# Display.net
KiCad netlist of a schematic drawn in Altium Designer
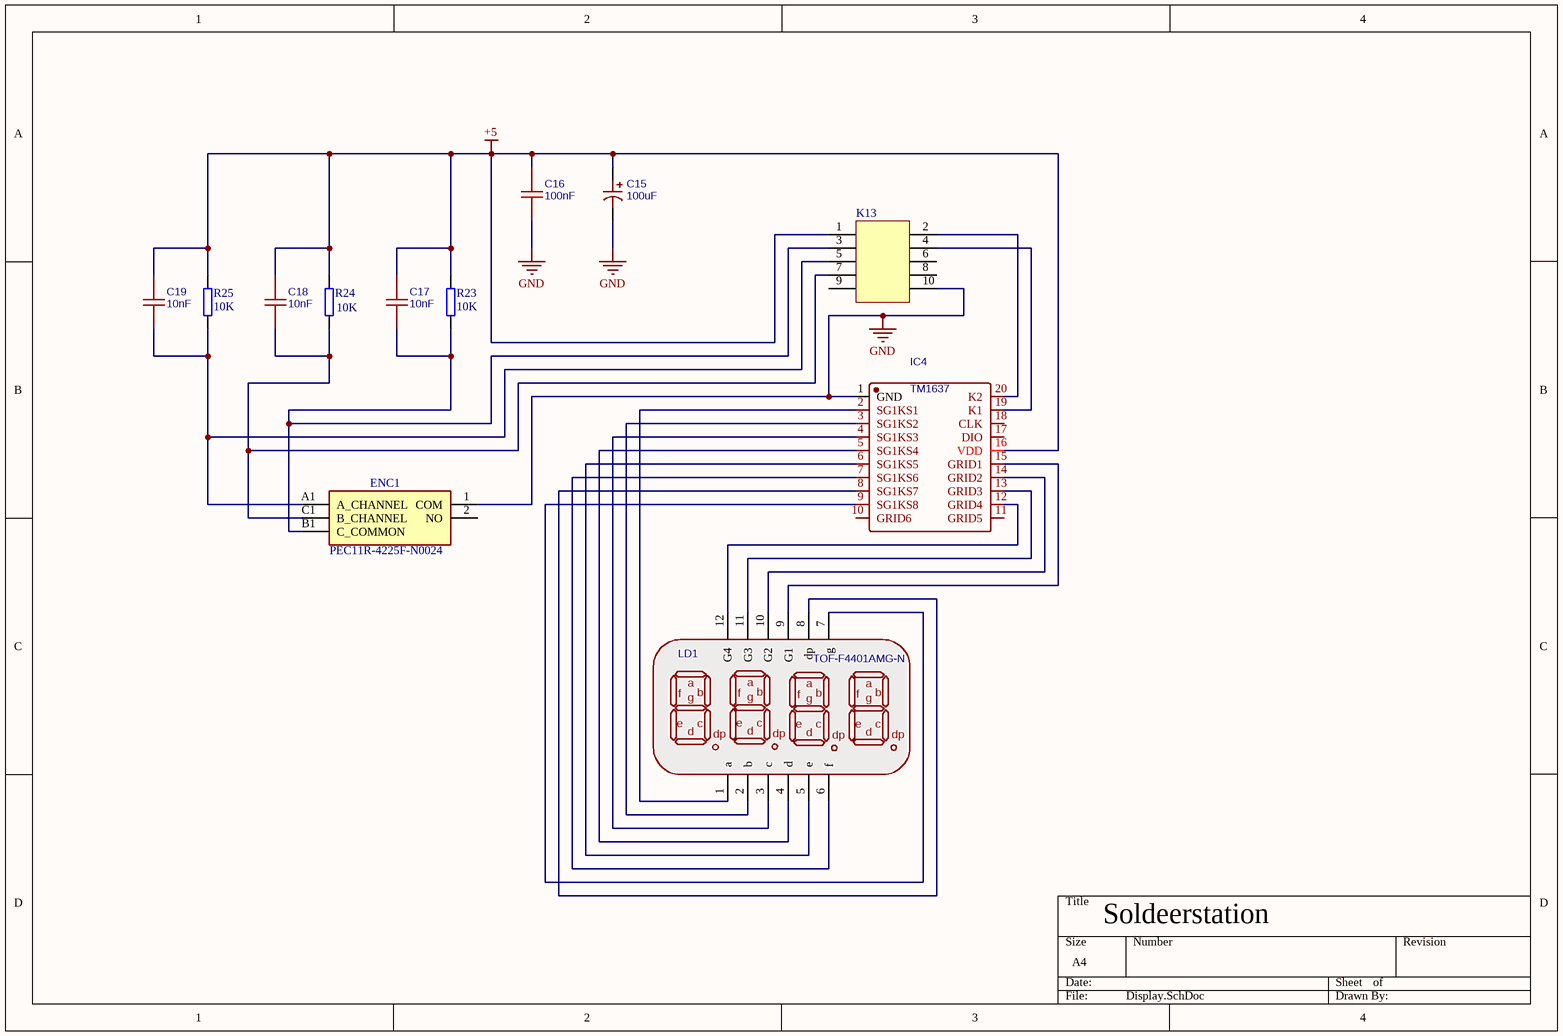
[diagram p0: Display.SchDoc]

(export (version "E")
  (design (tool "Eeschema 10.0.6"))
  (components
    (comp (ref "C15")
      (value "100uF")
      (footprint "C4 100uF")
      (fields
        (field (name "BOM_SUPPLIER PART") "C445063")
        (field (name "BOM_MANUFACTURER PART") "UWT1H101MNL1GS")
        (field (name "CONTRIBUTOR") "LCSC")
      )
      (libsource (lib "SoldeerStation") (part "C4 100uF"))
    )
    (comp (ref "C16")
      (value "100nF")
      (footprint "C6,7,12,13 10nF")
      (fields
        (field (name "BOM_SUPPLIER PART") "C376921")
        (field (name "BOM_MANUFACTURER PART") "TCC0805X7R103M500DT")
        (field (name "CONTRIBUTOR") "LCSC")
      )
      (libsource (lib "SoldeerStation") (part "C6,7,12,13 10nF"))
    )
    (comp (ref "C17")
      (value "10nF")
      (footprint "C6,7,12,13 10nF")
      (fields
        (field (name "BOM_SUPPLIER PART") "C376921")
        (field (name "BOM_MANUFACTURER PART") "TCC0805X7R103M500DT")
        (field (name "CONTRIBUTOR") "LCSC")
      )
      (libsource (lib "SoldeerStation") (part "C6,7,12,13 10nF"))
    )
    (comp (ref "C18")
      (value "10nF")
      (footprint "C6,7,12,13 10nF")
      (fields
        (field (name "BOM_SUPPLIER PART") "C376921")
        (field (name "BOM_MANUFACTURER PART") "TCC0805X7R103M500DT")
        (field (name "CONTRIBUTOR") "LCSC")
      )
      (libsource (lib "SoldeerStation") (part "C6,7,12,13 10nF"))
    )
    (comp (ref "C19")
      (value "10nF")
      (footprint "C6,7,12,13 10nF")
      (fields
        (field (name "BOM_SUPPLIER PART") "C376921")
        (field (name "BOM_MANUFACTURER PART") "TCC0805X7R103M500DT")
        (field (name "CONTRIBUTOR") "LCSC")
      )
      (libsource (lib "SoldeerStation") (part "C6,7,12,13 10nF"))
    )
    (comp (ref "ENC1")
      (value "PEC11R-4225F-N0024")
      (footprint "ENC1 draai encoder")
      (fields (field (name "MOUSER PART NUMBER") "652-PEC11R-4225F-N24"))
      (libsource (lib "SoldeerStation") (part "ENC1 Draai encoder"))
    )
    (comp (ref "IC4")
      (value "TM1637")
      (footprint "IC4 Led driver")
      (description "TM1637(TA2007)")
      (fields (field (name "BOM_SUPPLIER PART") "C5337160") (field (name "CONTRIBUTOR") "lcsc"))
      (libsource (lib "SoldeerStation") (part "IC4 Led driver"))
    )
    (comp (ref "K13")
      (value "~")
      (footprint "BOxHeader_10")
      (libsource (lib "SoldeerStation") (part "K Boxheader_10"))
    )
    (comp (ref "LD1")
      (value "TOF-F4401AMG-N")
      (footprint "LED1")
      (fields (field (name "BOM_SUPPLIER PART") "C325426") (field (name "CONTRIBUTOR") "LCSC"))
      (libsource (lib "SoldeerStation") (part "LED1"))
    )
    (comp (ref "R23")
      (value "10K")
      (footprint "RESC2013X50X30ML20T20")
      (fields (field (name "MANUFACTURER") "Vishay Dale") (field (name "PART NUMBER") "CRCW08050000Z0EA"))
      (libsource (lib "SoldeerStation") (part "R Resistor"))
    )
    (comp (ref "R24")
      (value "10K")
      (footprint "RESC2013X50X30ML20T20")
      (fields (field (name "MANUFACTURER") "Vishay Dale") (field (name "PART NUMBER") "CRCW08050000Z0EA"))
      (libsource (lib "SoldeerStation") (part "R Resistor"))
    )
    (comp (ref "R25")
      (value "10K")
      (footprint "RESC2013X50X30ML20T20")
      (fields (field (name "MANUFACTURER") "Vishay Dale") (field (name "PART NUMBER") "CRCW08050000Z0EA"))
      (libsource (lib "SoldeerStation") (part "R Resistor"))
    )
  )
  (nets
    (net (code "1") (name "+5") (class "Default")
      (node (ref "C15") (pin "1") (pinfunction "1_1") (pintype "passive"))
      (node (ref "C16") (pin "2") (pinfunction "2_2") (pintype "passive"))
      (node (ref "C17") (pin "2") (pinfunction "2_2") (pintype "passive"))
      (node (ref "C18") (pin "2") (pinfunction "2_2") (pintype "passive"))
      (node (ref "C19") (pin "2") (pinfunction "2_2") (pintype "passive"))
      (node (ref "IC4") (pin "16") (pinfunction "VDD_16") (pintype "passive"))
      (node (ref "K13") (pin "1") (pintype "passive"))
      (node (ref "R23") (pin "2") (pinfunction "2_2") (pintype "passive"))
      (node (ref "R24") (pin "2") (pinfunction "2_2") (pintype "passive"))
      (node (ref "R25") (pin "2") (pinfunction "2_2") (pintype "passive"))
    )
    (net (code "2") (name "GND") (class "Default")
      (node (ref "C15") (pin "2") (pinfunction "2_2") (pintype "passive"))
      (node (ref "C16") (pin "1") (pinfunction "1_1") (pintype "passive"))
      (node (ref "ENC1") (pin "1") (pinfunction "COM_1") (pintype "passive"))
      (node (ref "IC4") (pin "1") (pinfunction "GND_1") (pintype "passive"))
      (node (ref "K13") (pin "10") (pintype "passive"))
    )
    (net (code "3") (name "Net-(ENC1-A_CHANNEL)") (class "Default")
      (node (ref "C19") (pin "1") (pinfunction "1_1") (pintype "passive"))
      (node (ref "ENC1") (pin "A1") (pinfunction "A_CHANNEL_A1") (pintype "passive"))
      (node (ref "K13") (pin "5") (pintype "passive"))
      (node (ref "R25") (pin "1") (pinfunction "1_1") (pintype "passive"))
    )
    (net (code "4") (name "Net-(ENC1-B_CHANNEL)") (class "Default")
      (node (ref "C18") (pin "1") (pinfunction "1_1") (pintype "passive"))
      (node (ref "ENC1") (pin "C1") (pinfunction "B_CHANNEL_C1") (pintype "passive"))
      (node (ref "K13") (pin "7") (pintype "passive"))
      (node (ref "R24") (pin "1") (pinfunction "1_1") (pintype "passive"))
    )
    (net (code "5") (name "Net-(ENC1-C_COMMON)") (class "Default")
      (node (ref "C17") (pin "1") (pinfunction "1_1") (pintype "passive"))
      (node (ref "ENC1") (pin "B1") (pinfunction "C_COMMON_B1") (pintype "passive"))
      (node (ref "K13") (pin "3") (pintype "passive"))
      (node (ref "R23") (pin "1") (pinfunction "1_1") (pintype "passive"))
    )
    (net (code "6") (name "Net-(IC4-GRID1)") (class "Default")
      (node (ref "IC4") (pin "15") (pinfunction "GRID1_15") (pintype "passive"))
      (node (ref "LD1") (pin "9") (pinfunction "G1_9") (pintype "passive"))
    )
    (net (code "7") (name "Net-(IC4-GRID2)") (class "Default")
      (node (ref "IC4") (pin "14") (pinfunction "GRID2_14") (pintype "passive"))
      (node (ref "LD1") (pin "10") (pinfunction "G2_10") (pintype "passive"))
    )
    (net (code "8") (name "Net-(IC4-GRID3)") (class "Default")
      (node (ref "IC4") (pin "13") (pinfunction "GRID3_13") (pintype "passive"))
      (node (ref "LD1") (pin "11") (pinfunction "G3_11") (pintype "passive"))
    )
    (net (code "9") (name "Net-(IC4-GRID4)") (class "Default")
      (node (ref "IC4") (pin "12") (pinfunction "GRID4_12") (pintype "passive"))
      (node (ref "LD1") (pin "12") (pinfunction "G4_12") (pintype "passive"))
    )
    (net (code "10") (name "Net-(IC4-K1)") (class "Default")
      (node (ref "IC4") (pin "19") (pinfunction "K1_19") (pintype "passive"))
      (node (ref "K13") (pin "4") (pintype "passive"))
    )
    (net (code "11") (name "Net-(IC4-K2)") (class "Default")
      (node (ref "IC4") (pin "20") (pinfunction "K2_20") (pintype "passive"))
      (node (ref "K13") (pin "2") (pintype "passive"))
    )
    (net (code "12") (name "Net-(IC4-SG1KS1)") (class "Default")
      (node (ref "IC4") (pin "2") (pinfunction "SG1KS1_2") (pintype "passive"))
      (node (ref "LD1") (pin "1") (pinfunction "a_1") (pintype "passive"))
    )
    (net (code "13") (name "Net-(IC4-SG1KS2)") (class "Default")
      (node (ref "IC4") (pin "3") (pinfunction "SG1KS2_3") (pintype "passive"))
      (node (ref "LD1") (pin "2") (pinfunction "b_2") (pintype "passive"))
    )
    (net (code "14") (name "Net-(IC4-SG1KS3)") (class "Default")
      (node (ref "IC4") (pin "4") (pinfunction "SG1KS3_4") (pintype "passive"))
      (node (ref "LD1") (pin "3") (pinfunction "c_3") (pintype "passive"))
    )
    (net (code "15") (name "Net-(IC4-SG1KS4)") (class "Default")
      (node (ref "IC4") (pin "5") (pinfunction "SG1KS4_5") (pintype "passive"))
      (node (ref "LD1") (pin "4") (pinfunction "d_4") (pintype "passive"))
    )
    (net (code "16") (name "Net-(IC4-SG1KS5)") (class "Default")
      (node (ref "IC4") (pin "6") (pinfunction "SG1KS5_6") (pintype "passive"))
      (node (ref "LD1") (pin "5") (pinfunction "e_5") (pintype "passive"))
    )
    (net (code "17") (name "Net-(IC4-SG1KS6)") (class "Default")
      (node (ref "IC4") (pin "7") (pinfunction "SG1KS6_7") (pintype "passive"))
      (node (ref "LD1") (pin "6") (pinfunction "f_6") (pintype "passive"))
    )
    (net (code "18") (name "Net-(IC4-SG1KS7)") (class "Default")
      (node (ref "IC4") (pin "8") (pinfunction "SG1KS7_8") (pintype "passive"))
      (node (ref "LD1") (pin "8") (pinfunction "dp_8") (pintype "passive"))
    )
    (net (code "19") (name "Net-(IC4-SG1KS8)") (class "Default")
      (node (ref "IC4") (pin "9") (pinfunction "SG1KS8_9") (pintype "passive"))
      (node (ref "LD1") (pin "7") (pinfunction "g_7") (pintype "passive"))
    )
    (net (code "20") (name "unconnected-(ENC1-NO-Pad2)") (class "Default")
      (node (ref "ENC1") (pin "2") (pinfunction "NO_2") (pintype "passive"))
    )
    (net (code "21") (name "unconnected-(IC4-CLK-Pad18)") (class "Default")
      (node (ref "IC4") (pin "18") (pinfunction "CLK_18") (pintype "passive"))
    )
    (net (code "22") (name "unconnected-(IC4-DIO-Pad17)") (class "Default")
      (node (ref "IC4") (pin "17") (pinfunction "DIO_17") (pintype "passive"))
    )
    (net (code "23") (name "unconnected-(IC4-GRID5-Pad11)") (class "Default")
      (node (ref "IC4") (pin "11") (pinfunction "GRID5_11") (pintype "passive"))
    )
    (net (code "24") (name "unconnected-(IC4-GRID6-Pad10)") (class "Default")
      (node (ref "IC4") (pin "10") (pinfunction "GRID6_10") (pintype "passive"))
    )
    (net (code "25") (name "unconnected-(K13-Pad6)") (class "Default")
      (node (ref "K13") (pin "6") (pintype "passive"))
    )
    (net (code "26") (name "unconnected-(K13-Pad8)") (class "Default")
      (node (ref "K13") (pin "8") (pintype "passive"))
    )
    (net (code "27") (name "unconnected-(K13-Pad9)") (class "Default")
      (node (ref "K13") (pin "9") (pintype "passive"))
    )
  )
)
